# oneboard4.net
KiCad netlist of a schematic drawn in EAGLE
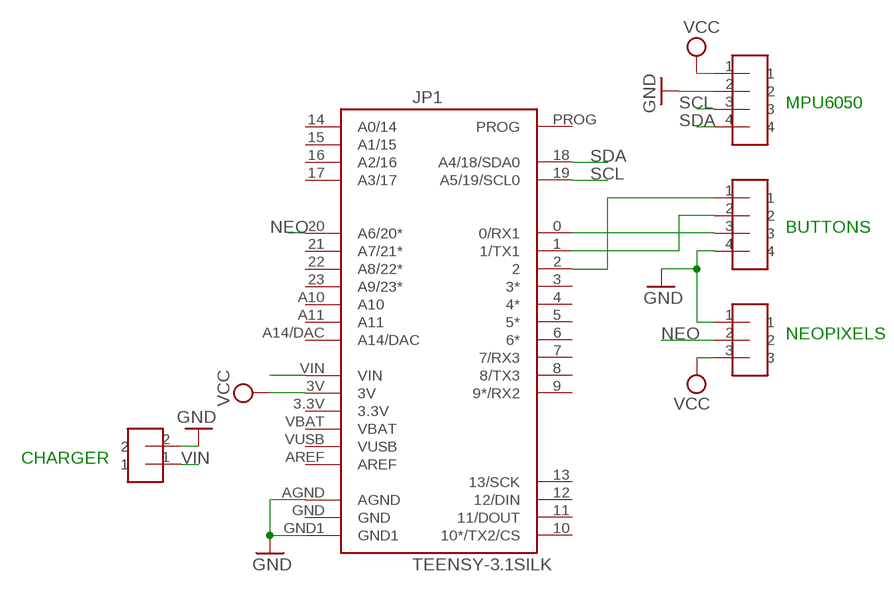
[diagram p0: schematic, sheet 1]

(export (version "E")
  (design (tool "Eeschema 10.0.6"))
  (components
    (comp (ref "JP1")
      (value "TEENSY-3.1SILK")
      (footprint "eagle-import:TEENSY-3.1")
      (libsource (lib "eagle-import") (part "TEENSY-3.1SILK"))
    )
    (comp (ref "U$2")
      (value "HEADER-3")
      (footprint "eagle-import:HEADER-3")
      (libsource (lib "eagle-import") (part "HEADER-3"))
    )
    (comp (ref "U$3")
      (value "HEADER-2")
      (footprint "eagle-import:HEADER-2")
      (libsource (lib "eagle-import") (part "HEADER-2"))
    )
    (comp (ref "U$4")
      (value "HEADER-4")
      (footprint "eagle-import:HEADER-4")
      (libsource (lib "eagle-import") (part "HEADER-4"))
    )
    (comp (ref "U$5")
      (value "HEADER-4")
      (footprint "eagle-import:HEADER-4")
      (libsource (lib "eagle-import") (part "HEADER-4"))
    )
  )
  (nets
    (net (code "1") (name "/NEO") (class "Default")
      (node (ref "JP1") (pin "20") (pinfunction "A6/20*_20") (pintype "bidirectional"))
      (node (ref "U$2") (pin "2") (pinfunction "2_2") (pintype "bidirectional"))
    )
    (net (code "2") (name "/SCL") (class "Default")
      (node (ref "JP1") (pin "19") (pinfunction "A5/19/SCL0_19") (pintype "bidirectional"))
      (node (ref "U$4") (pin "3") (pinfunction "3_3") (pintype "bidirectional"))
    )
    (net (code "3") (name "/SDA") (class "Default")
      (node (ref "JP1") (pin "18") (pinfunction "A4/18/SDA0_18") (pintype "bidirectional"))
      (node (ref "U$4") (pin "4") (pinfunction "4_4") (pintype "bidirectional"))
    )
    (net (code "4") (name "/VIN") (class "Default")
      (node (ref "JP1") (pin "VIN") (pinfunction "VIN_VIN") (pintype "bidirectional"))
      (node (ref "U$3") (pin "1") (pinfunction "1_1") (pintype "bidirectional"))
    )
    (net (code "5") (name "GND") (class "Default")
      (node (ref "JP1") (pin "AGND") (pinfunction "AGND_AGND") (pintype "bidirectional"))
      (node (ref "JP1") (pin "GND1") (pinfunction "GND1_GND1") (pintype "bidirectional"))
      (node (ref "U$2") (pin "1") (pinfunction "1_1") (pintype "bidirectional"))
      (node (ref "U$3") (pin "2") (pinfunction "2_2") (pintype "bidirectional"))
      (node (ref "U$4") (pin "2") (pinfunction "2_2") (pintype "bidirectional"))
      (node (ref "U$5") (pin "4") (pinfunction "4_4") (pintype "bidirectional"))
    )
    (net (code "6") (name "Net-(JP1-0{slash}RX1)") (class "Default")
      (node (ref "JP1") (pin "0") (pinfunction "0/RX1_0") (pintype "bidirectional"))
      (node (ref "U$5") (pin "3") (pinfunction "3_3") (pintype "bidirectional"))
    )
    (net (code "7") (name "Net-(JP1-1{slash}TX1)") (class "Default")
      (node (ref "JP1") (pin "1") (pinfunction "1/TX1_1") (pintype "bidirectional"))
      (node (ref "U$5") (pin "2") (pinfunction "2_2") (pintype "bidirectional"))
    )
    (net (code "8") (name "Net-(JP1-Pad2)") (class "Default")
      (node (ref "JP1") (pin "2") (pinfunction "2_2") (pintype "bidirectional"))
      (node (ref "U$5") (pin "1") (pinfunction "1_1") (pintype "bidirectional"))
    )
    (net (code "9") (name "VCC") (class "Default")
      (node (ref "JP1") (pin "3V") (pinfunction "3V_3V") (pintype "bidirectional"))
      (node (ref "U$2") (pin "3") (pinfunction "3_3") (pintype "bidirectional"))
      (node (ref "U$4") (pin "1") (pinfunction "1_1") (pintype "bidirectional"))
    )
    (net (code "10") (name "unconnected-(JP1-3*-Pad3)") (class "Default")
      (node (ref "JP1") (pin "3") (pinfunction "3*_3") (pintype "bidirectional"))
    )
    (net (code "11") (name "unconnected-(JP1-4*-Pad4)") (class "Default")
      (node (ref "JP1") (pin "4") (pinfunction "4*_4") (pintype "bidirectional"))
    )
    (net (code "12") (name "unconnected-(JP1-5*-Pad5)") (class "Default")
      (node (ref "JP1") (pin "5") (pinfunction "5*_5") (pintype "bidirectional"))
    )
    (net (code "13") (name "unconnected-(JP1-6*-Pad6)") (class "Default")
      (node (ref "JP1") (pin "6") (pinfunction "6*_6") (pintype "bidirectional"))
    )
    (net (code "14") (name "unconnected-(JP1-7{slash}RX3-Pad7)") (class "Default")
      (node (ref "JP1") (pin "7") (pinfunction "7/RX3_7") (pintype "bidirectional"))
    )
    (net (code "15") (name "unconnected-(JP1-8{slash}TX3-Pad8)") (class "Default")
      (node (ref "JP1") (pin "8") (pinfunction "8/TX3_8") (pintype "bidirectional"))
    )
    (net (code "16") (name "unconnected-(JP1-9*{slash}RX2-Pad9)") (class "Default")
      (node (ref "JP1") (pin "9") (pinfunction "9*/RX2_9") (pintype "bidirectional"))
    )
    (net (code "17") (name "unconnected-(JP1-10*{slash}TX2{slash}CS-Pad10)") (class "Default")
      (node (ref "JP1") (pin "10") (pinfunction "10*/TX2/CS_10") (pintype "bidirectional"))
    )
    (net (code "18") (name "unconnected-(JP1-11{slash}DOUT-Pad11)") (class "Default")
      (node (ref "JP1") (pin "11") (pinfunction "11/DOUT_11") (pintype "bidirectional"))
    )
    (net (code "19") (name "unconnected-(JP1-12{slash}DIN-Pad12)") (class "Default")
      (node (ref "JP1") (pin "12") (pinfunction "12/DIN_12") (pintype "bidirectional"))
    )
    (net (code "20") (name "unconnected-(JP1-13{slash}SCK-Pad13)") (class "Default")
      (node (ref "JP1") (pin "13") (pinfunction "13/SCK_13") (pintype "bidirectional"))
    )
    (net (code "21") (name "unconnected-(JP1-A0{slash}14-Pad14)") (class "Default")
      (node (ref "JP1") (pin "14") (pinfunction "A0/14_14") (pintype "bidirectional"))
    )
    (net (code "22") (name "unconnected-(JP1-A1{slash}15-Pad15)") (class "Default")
      (node (ref "JP1") (pin "15") (pinfunction "A1/15_15") (pintype "bidirectional"))
    )
    (net (code "23") (name "unconnected-(JP1-A2{slash}16-Pad16)") (class "Default")
      (node (ref "JP1") (pin "16") (pinfunction "A2/16_16") (pintype "bidirectional"))
    )
    (net (code "24") (name "unconnected-(JP1-A3{slash}17-Pad17)") (class "Default")
      (node (ref "JP1") (pin "17") (pinfunction "A3/17_17") (pintype "bidirectional"))
    )
    (net (code "25") (name "unconnected-(JP1-A7{slash}21*-Pad21)") (class "Default")
      (node (ref "JP1") (pin "21") (pinfunction "A7/21*_21") (pintype "bidirectional"))
    )
    (net (code "26") (name "unconnected-(JP1-A8{slash}22*-Pad22)") (class "Default")
      (node (ref "JP1") (pin "22") (pinfunction "A8/22*_22") (pintype "bidirectional"))
    )
    (net (code "27") (name "unconnected-(JP1-A9{slash}23*-Pad23)") (class "Default")
      (node (ref "JP1") (pin "23") (pinfunction "A9/23*_23") (pintype "bidirectional"))
    )
    (net (code "28") (name "unconnected-(JP1-Pad3.3V)") (class "Default")
      (node (ref "JP1") (pin "3.3V") (pinfunction "3.3V_3.3V") (pintype "bidirectional"))
    )
    (net (code "29") (name "unconnected-(JP1-PadA10)") (class "Default")
      (node (ref "JP1") (pin "A10") (pinfunction "A10_A10") (pintype "bidirectional"))
    )
    (net (code "30") (name "unconnected-(JP1-PadA11)") (class "Default")
      (node (ref "JP1") (pin "A11") (pinfunction "A11_A11") (pintype "bidirectional"))
    )
    (net (code "31") (name "unconnected-(JP1-PadA14{slash}DAC)") (class "Default")
      (node (ref "JP1") (pin "A14/DAC") (pinfunction "A14/DAC_A14/DAC") (pintype "bidirectional"))
    )
    (net (code "32") (name "unconnected-(JP1-PadAREF)") (class "Default")
      (node (ref "JP1") (pin "AREF") (pinfunction "AREF_AREF") (pintype "bidirectional"))
    )
    (net (code "33") (name "unconnected-(JP1-PadGND)") (class "Default")
      (node (ref "JP1") (pin "GND") (pinfunction "GND_GND") (pintype "bidirectional"))
    )
    (net (code "34") (name "unconnected-(JP1-PadPROG)") (class "Default")
      (node (ref "JP1") (pin "PROG") (pinfunction "PROG_PROG") (pintype "bidirectional"))
    )
    (net (code "35") (name "unconnected-(JP1-PadVBAT)") (class "Default")
      (node (ref "JP1") (pin "VBAT") (pinfunction "VBAT_VBAT") (pintype "bidirectional"))
    )
    (net (code "36") (name "unconnected-(JP1-PadVUSB)") (class "Default")
      (node (ref "JP1") (pin "VUSB") (pinfunction "VUSB_VUSB") (pintype "bidirectional"))
    )
  )
)
